# SENSOR.net
KiCad netlist of a schematic drawn in Altium Designer
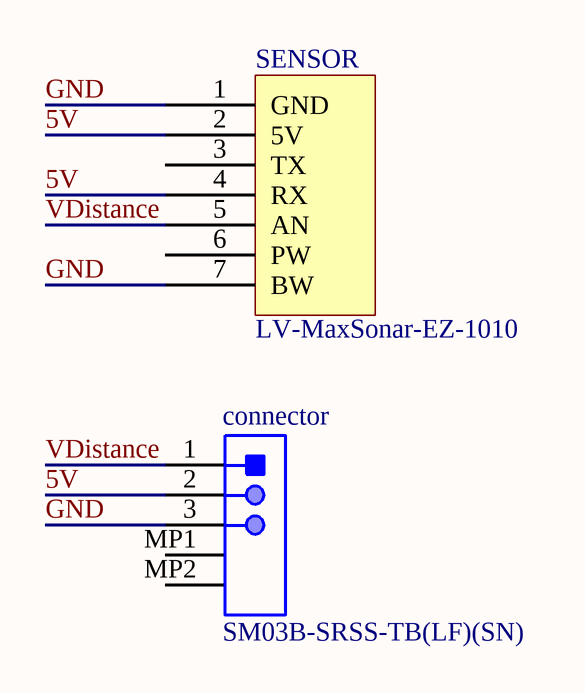
[diagram p0: SENSOR.SchDoc]

(export (version "E")
  (design (tool "Eeschema 10.0.6"))
  (components
    (comp (ref "connector")
      (value "SM03B-SRSS-TB(LF)(SN)")
      (footprint "JST-SM03B-SRSS-TB_V")
      (description "Male Header, Pitch 1 mm, 1 x 3 Position, Height 2.9 mm, -25 to 85 degC, RoHS, Tape and Reel")
      (fields (field (name "MANUFACTURER") "JST"))
      (libsource (lib "Altium Content Vault") (part "CN-1P-2M-R3"))
    )
    (comp (ref "SENSOR")
      (value "LV-MaxSonar-EZ-1010")
      (footprint "LV-MaxSonar-EZ-1010-Footprint-1")
      (description "Ultrasonic sensor")
      (libsource (lib "Evan Chang work on PCB") (part "LV-Ma-Symbol-1"))
    )
  )
  (nets
    (net (code "1") (name "/5V") (class "Default")
      (node (ref "SENSOR") (pin "2") (pinfunction "5V_2") (pintype "passive"))
      (node (ref "SENSOR") (pin "4") (pinfunction "RX_4") (pintype "passive"))
      (node (ref "connector") (pin "2") (pinfunction "2_2") (pintype "passive"))
    )
    (net (code "2") (name "/GND") (class "Default")
      (node (ref "SENSOR") (pin "1") (pinfunction "GND_1") (pintype "passive"))
      (node (ref "SENSOR") (pin "7") (pinfunction "BW_7") (pintype "passive"))
      (node (ref "connector") (pin "3") (pinfunction "3_3") (pintype "passive"))
    )
    (net (code "3") (name "/VDistance") (class "Default")
      (node (ref "SENSOR") (pin "5") (pinfunction "AN_5") (pintype "passive"))
      (node (ref "connector") (pin "1") (pinfunction "1_1") (pintype "passive"))
    )
    (net (code "4") (name "unconnected-(SENSOR-PW-Pad6)") (class "Default")
      (node (ref "SENSOR") (pin "6") (pinfunction "PW_6") (pintype "passive"))
    )
    (net (code "5") (name "unconnected-(SENSOR-TX-Pad3)") (class "Default")
      (node (ref "SENSOR") (pin "3") (pinfunction "TX_3") (pintype "passive"))
    )
    (net (code "6") (name "unconnected-(connector-PadMP1)") (class "Default")
      (node (ref "connector") (pin "MP1") (pinfunction "MP1_MP1") (pintype "passive"))
    )
    (net (code "7") (name "unconnected-(connector-PadMP2)") (class "Default")
      (node (ref "connector") (pin "MP2") (pinfunction "MP2_MP2") (pintype "passive"))
    )
  )
)
